# TPS22810_breakout.net
KiCad netlist of a schematic drawn in EAGLE
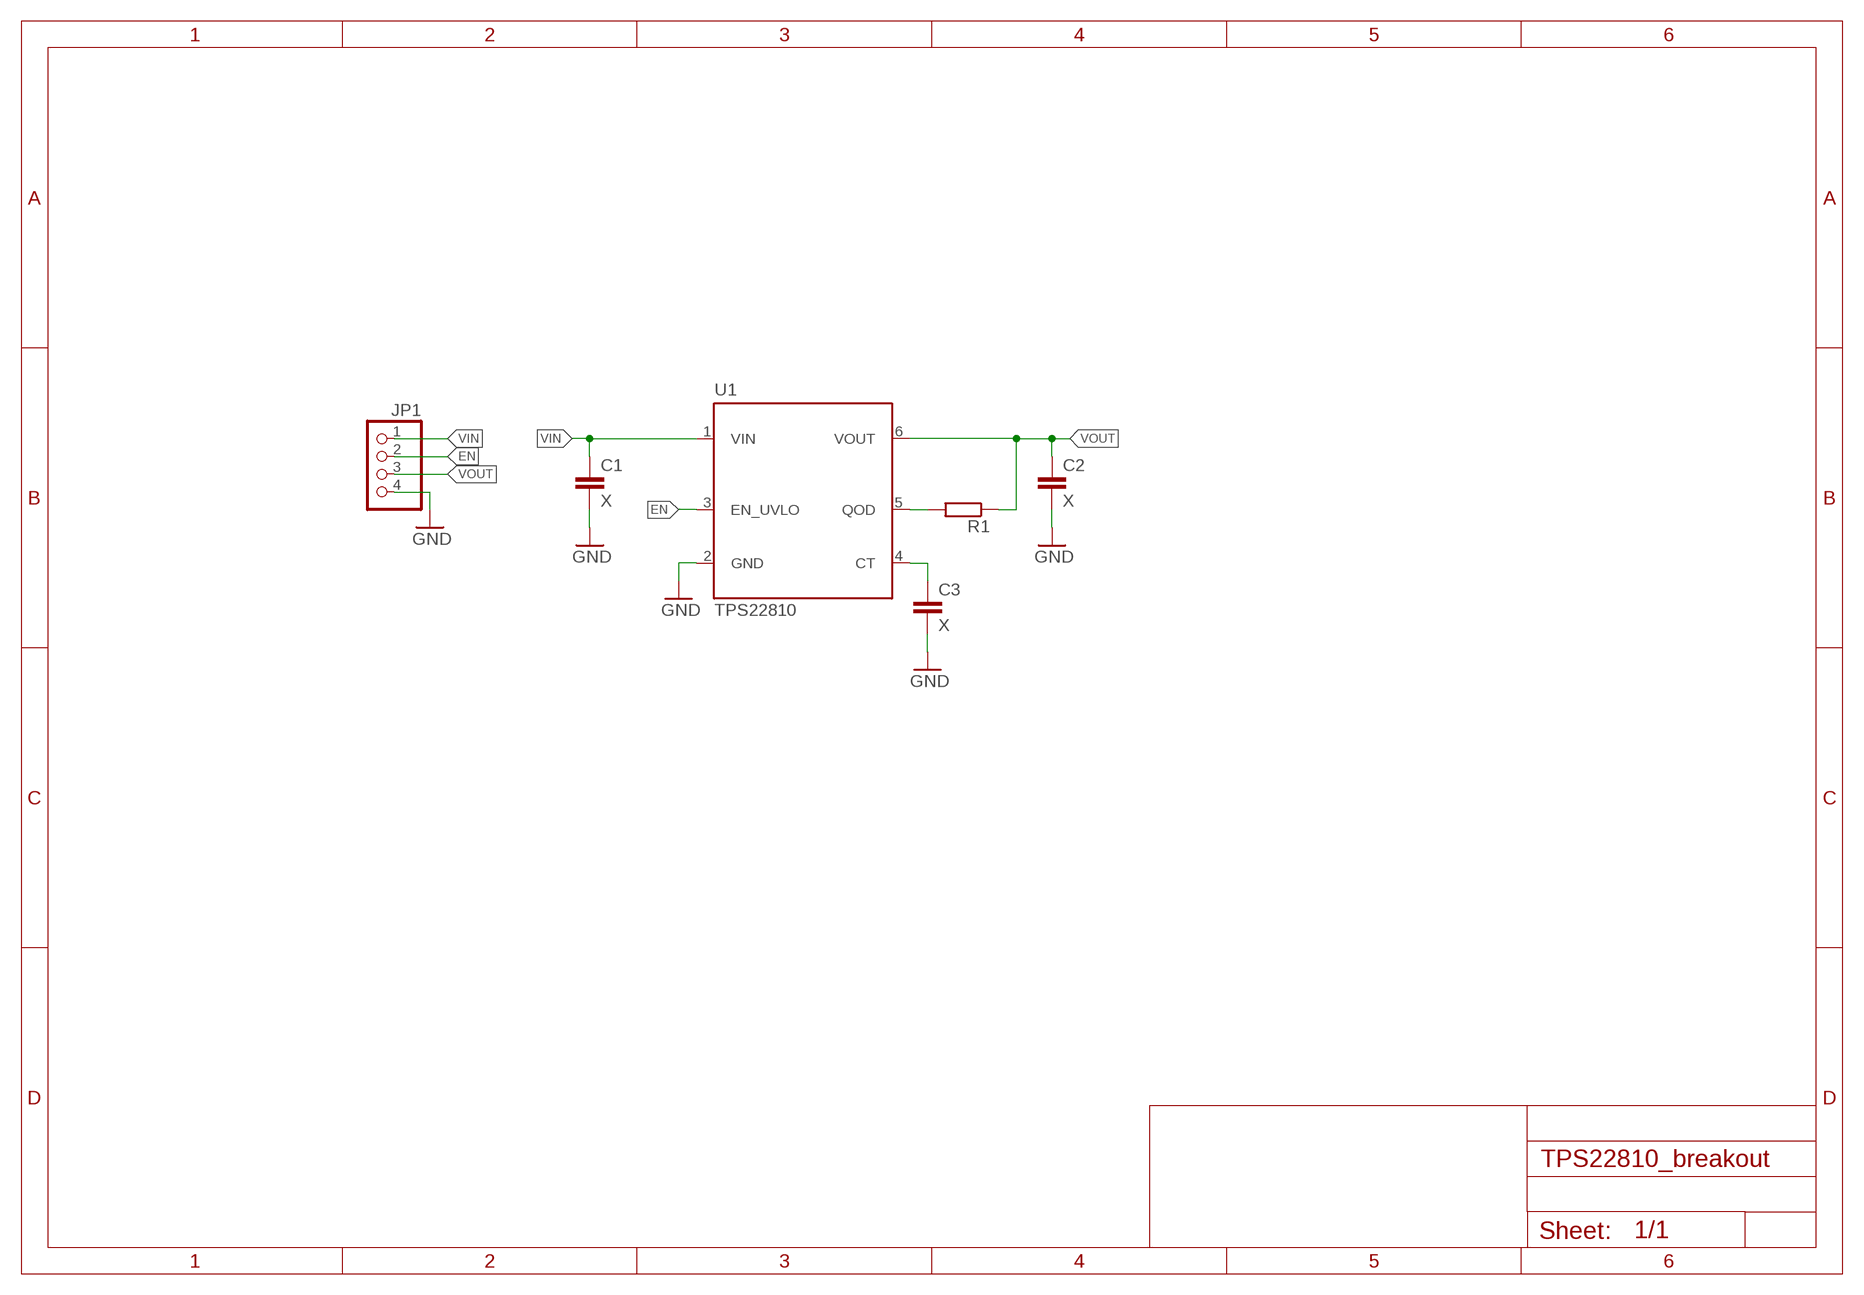
[diagram p0: schematic, sheet 1]

(export (version "E")
  (design (tool "Eeschema 10.0.6"))
  (components
    (comp (ref "C1")
      (value "X")
      (footprint "eagle-import:C0603")
      (libsource (lib "eagle-import") (part "C-EU0603"))
    )
    (comp (ref "C2")
      (value "X")
      (footprint "eagle-import:C0603")
      (libsource (lib "eagle-import") (part "C-EU0603"))
    )
    (comp (ref "C3")
      (value "X")
      (footprint "eagle-import:C0603")
      (libsource (lib "eagle-import") (part "C-EU0603"))
    )
    (comp (ref "JP1")
      (value "PINHD-1X4")
      (footprint "eagle-import:1X04")
      (libsource (lib "eagle-import") (part "PINHD-1X4"))
    )
    (comp (ref "R1")
      (value "R-EU_R0603")
      (footprint "eagle-import:R0603")
      (libsource (lib "eagle-import") (part "R-EU_R0603"))
    )
    (comp (ref "U1")
      (value "TPS22810")
      (footprint "eagle-import:DBV-R-PDSO-G6")
      (libsource (lib "eagle-import") (part "TPS22810"))
    )
  )
  (nets
    (net (code "1") (name "EN") (class "Default")
      (node (ref "JP1") (pin "2") (pinfunction "2_2") (pintype "passive"))
      (node (ref "U1") (pin "3") (pinfunction "EN_UVLO_3") (pintype "passive"))
    )
    (net (code "2") (name "GND") (class "Default")
      (node (ref "C1") (pin "2") (pinfunction "2_2") (pintype "passive"))
      (node (ref "C2") (pin "2") (pinfunction "2_2") (pintype "passive"))
      (node (ref "C3") (pin "2") (pinfunction "2_2") (pintype "passive"))
      (node (ref "JP1") (pin "4") (pinfunction "4_4") (pintype "passive"))
      (node (ref "U1") (pin "2") (pinfunction "GND_2") (pintype "passive"))
    )
    (net (code "3") (name "Net-(U1-CT)") (class "Default")
      (node (ref "C3") (pin "1") (pinfunction "1_1") (pintype "passive"))
      (node (ref "U1") (pin "4") (pinfunction "CT_4") (pintype "passive"))
    )
    (net (code "4") (name "Net-(U1-QOD)") (class "Default")
      (node (ref "R1") (pin "2") (pinfunction "2_2") (pintype "passive"))
      (node (ref "U1") (pin "5") (pinfunction "QOD_5") (pintype "passive"))
    )
    (net (code "5") (name "VIN") (class "Default")
      (node (ref "C1") (pin "1") (pinfunction "1_1") (pintype "passive"))
      (node (ref "JP1") (pin "1") (pinfunction "1_1") (pintype "passive"))
      (node (ref "U1") (pin "1") (pinfunction "VIN_1") (pintype "passive"))
    )
    (net (code "6") (name "VOUT") (class "Default")
      (node (ref "C2") (pin "1") (pinfunction "1_1") (pintype "passive"))
      (node (ref "JP1") (pin "3") (pinfunction "3_3") (pintype "passive"))
      (node (ref "R1") (pin "1") (pinfunction "1_1") (pintype "passive"))
      (node (ref "U1") (pin "6") (pinfunction "VOUT_6") (pintype "passive"))
    )
  )
)
